# STM32G474RBT6.net
KiCad netlist of a schematic drawn in EasyEDA Pro
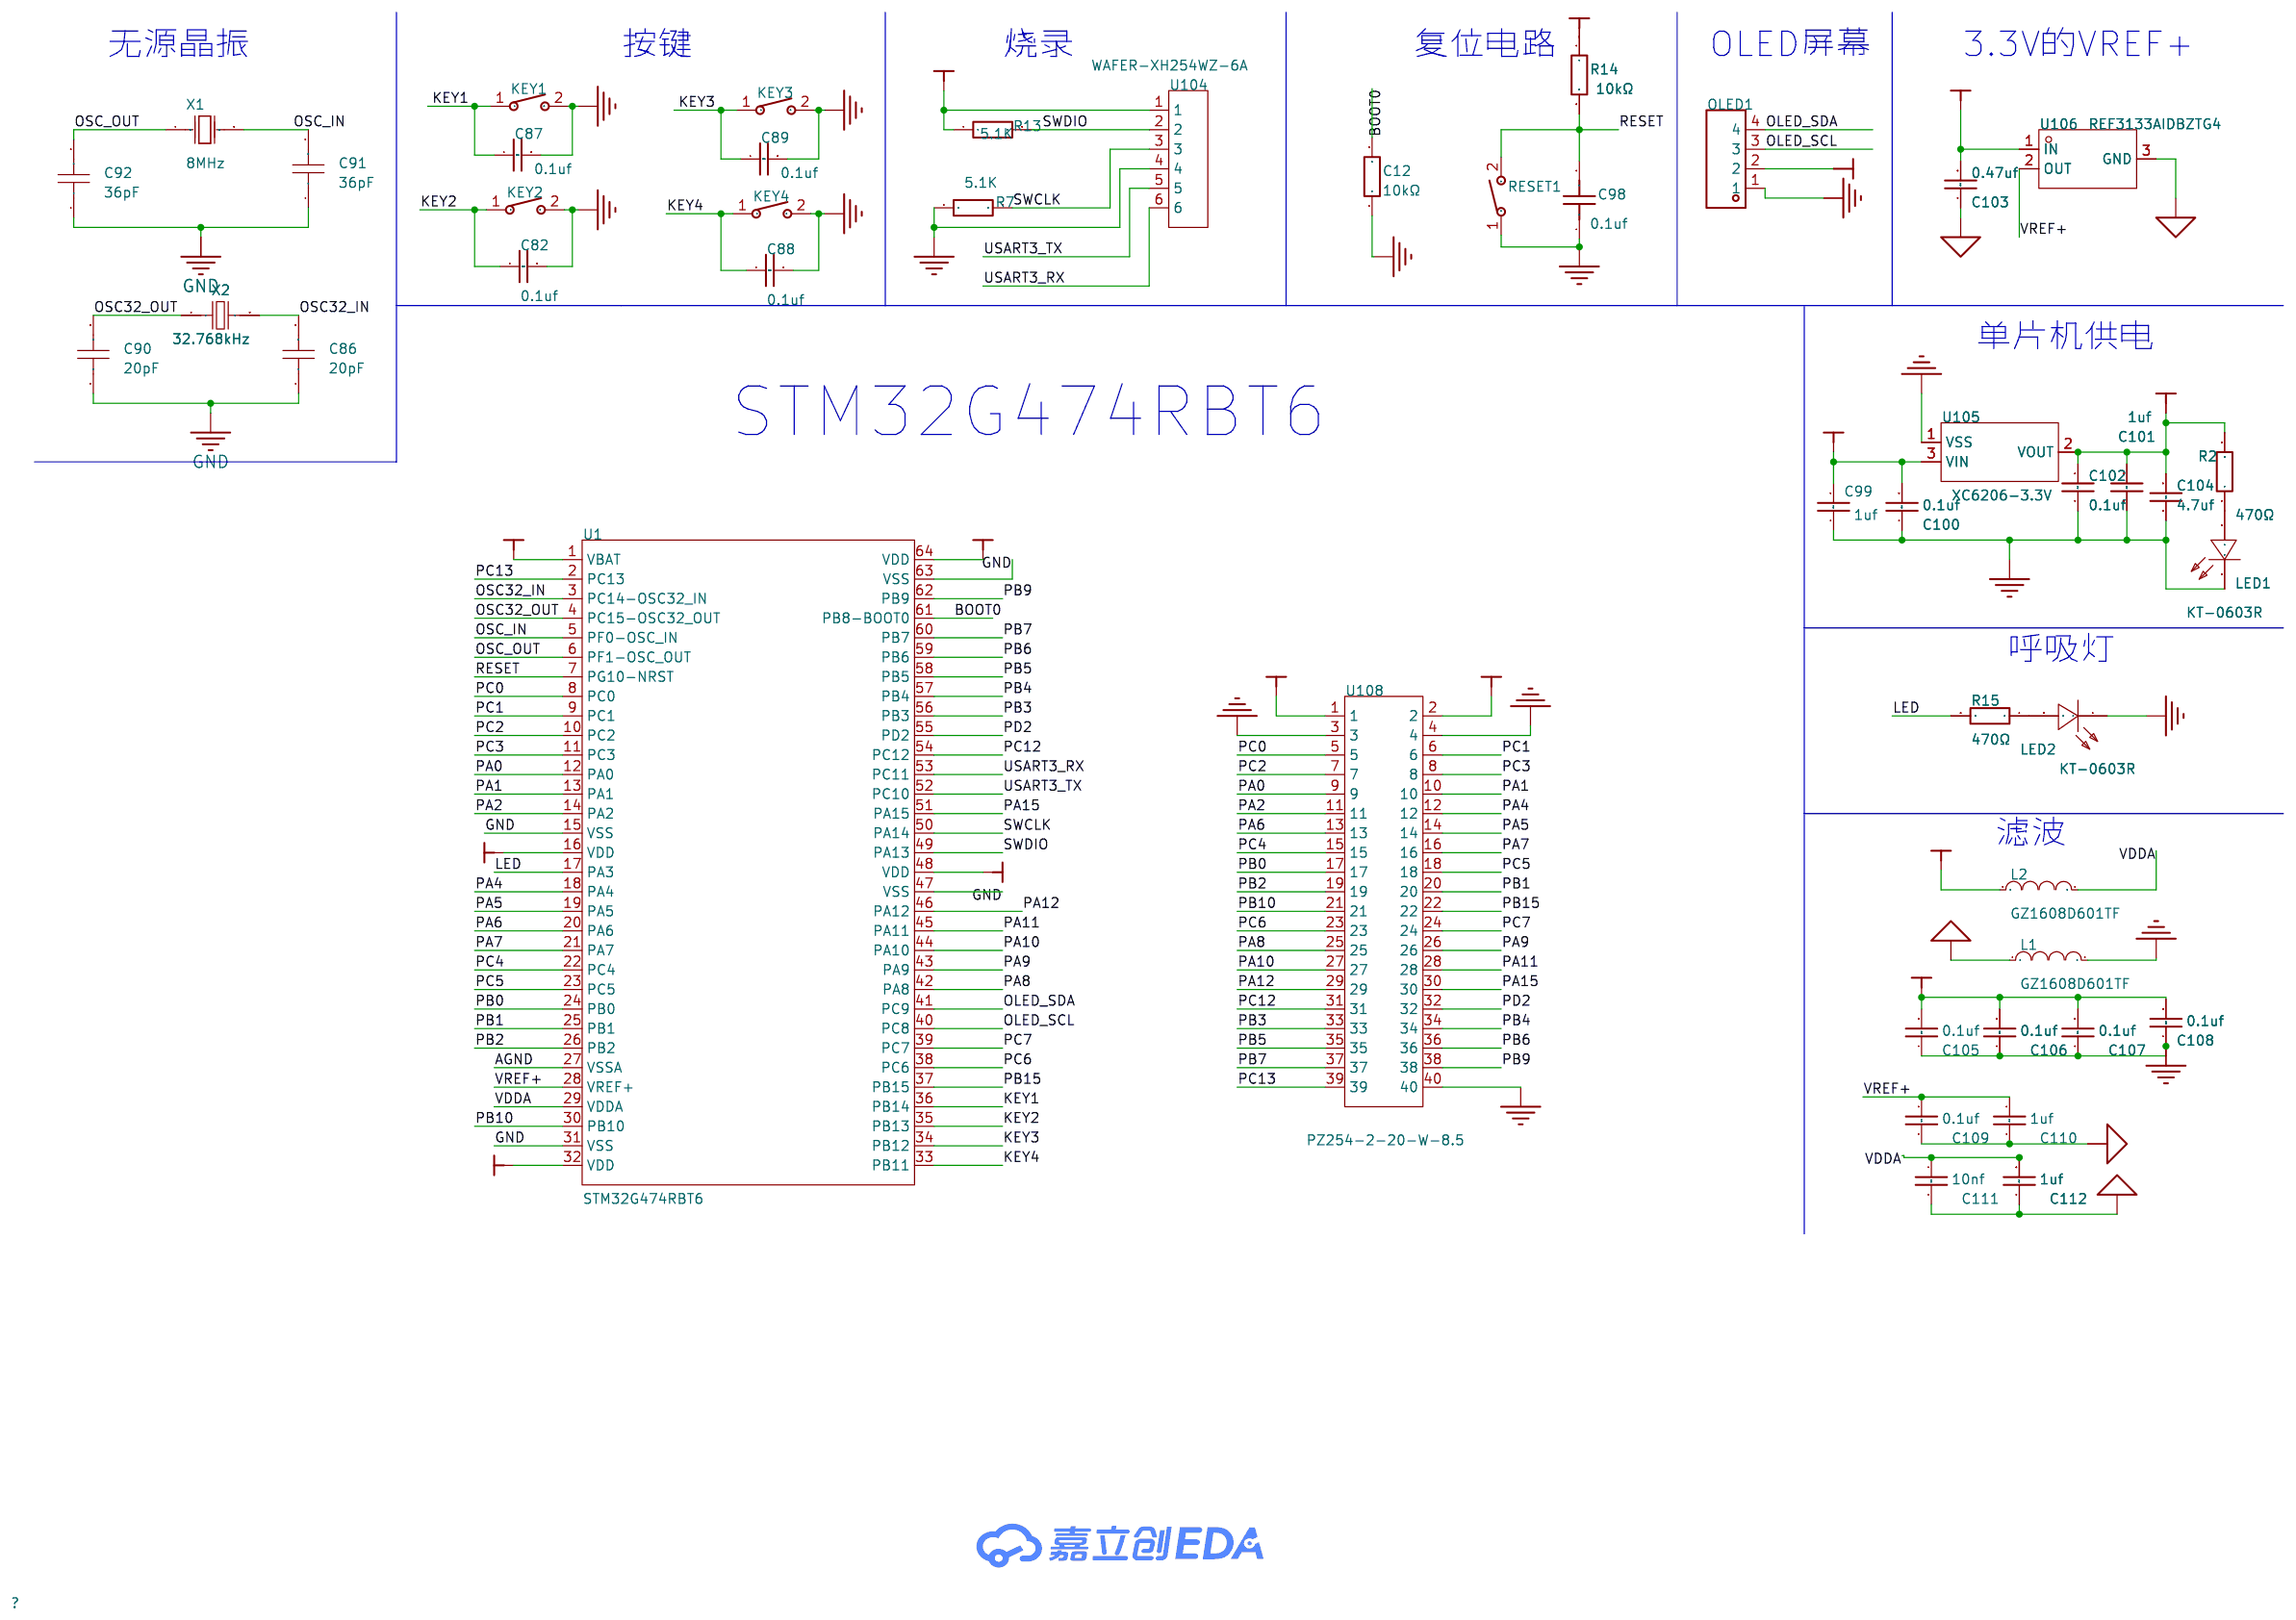
[diagram p0: schematic sheet]

(export (version "E")
  (design (tool "Eeschema 10.0.6"))
  (components
    (comp (ref "C12")
      (value "10kΩ")
      (footprint "easyedapro:R0805")
      (fields
        (field (name "Manufacturer Part") "0805W8F1002T5E")
        (field (name "Manufacturer") "UNI-ROYAL(厚声)")
      )
      (libsource (lib "easyedapro") (part "0805W8F1002T5E"))
    )
    (comp (ref "C82")
      (value "0.1uf")
      (footprint "easyedapro:C0603")
      (libsource (lib "easyedapro") (part "C0603"))
    )
    (comp (ref "C86")
      (value "20pF")
      (footprint "easyedapro:C0603")
      (description "容值:47pF;精度:±5%;额定电压:100V;温度系数:C0G;")
      (fields
        (field (name "Manufacturer Part") "CAI0603C0G470J101JT")
        (field (name "Manufacturer") "HRE(芯声)")
      )
      (libsource (lib "easyedapro") (part "CAI0603C0G470J101JT"))
    )
    (comp (ref "C87")
      (value "0.1uf")
      (footprint "easyedapro:C0603")
      (libsource (lib "easyedapro") (part "C0603"))
    )
    (comp (ref "C88")
      (value "0.1uf")
      (footprint "easyedapro:C0603")
      (libsource (lib "easyedapro") (part "C0603"))
    )
    (comp (ref "C89")
      (value "0.1uf")
      (footprint "easyedapro:C0603")
      (libsource (lib "easyedapro") (part "C0603"))
    )
    (comp (ref "C90")
      (value "20pF")
      (footprint "easyedapro:C0603")
      (description "容值:47pF;精度:±5%;额定电压:100V;温度系数:C0G;")
      (fields
        (field (name "Manufacturer Part") "CAI0603C0G470J101JT")
        (field (name "Manufacturer") "HRE(芯声)")
      )
      (libsource (lib "easyedapro") (part "CAI0603C0G470J101JT"))
    )
    (comp (ref "C91")
      (value "36pF")
      (footprint "easyedapro:C0603")
      (description "容值:47pF;精度:±5%;额定电压:100V;温度系数:C0G;")
      (fields
        (field (name "Manufacturer Part") "CAI0603C0G470J101JT")
        (field (name "Manufacturer") "HRE(芯声)")
      )
      (libsource (lib "easyedapro") (part "CAI0603C0G470J101JT"))
    )
    (comp (ref "C92")
      (value "36pF")
      (footprint "easyedapro:C0603")
      (description "容值:47pF;精度:±5%;额定电压:100V;温度系数:C0G;")
      (fields
        (field (name "Manufacturer Part") "CAI0603C0G470J101JT")
        (field (name "Manufacturer") "HRE(芯声)")
      )
      (libsource (lib "easyedapro") (part "CAI0603C0G470J101JT"))
    )
    (comp (ref "C98") (value "0.1uf") (footprint "easyedapro:电容") (libsource (lib "easyedapro") (part "电容")))
    (comp (ref "C99")
      (value "1uf")
      (footprint "easyedapro:C0603")
      (libsource (lib "easyedapro") (part "C0603"))
    )
    (comp (ref "C100")
      (value "0.1uf")
      (footprint "easyedapro:C0603")
      (libsource (lib "easyedapro") (part "C0603"))
    )
    (comp (ref "C101")
      (value "1uf")
      (footprint "easyedapro:C0603")
      (libsource (lib "easyedapro") (part "C0603"))
    )
    (comp (ref "C102")
      (value "0.1uf")
      (footprint "easyedapro:C0603")
      (libsource (lib "easyedapro") (part "C0603"))
    )
    (comp (ref "C103")
      (value "0.47uf")
      (footprint "easyedapro:C0603")
      (libsource (lib "easyedapro") (part "C0603"))
    )
    (comp (ref "C104")
      (value "4.7uf")
      (footprint "easyedapro:C0603")
      (libsource (lib "easyedapro") (part "C0603"))
    )
    (comp (ref "C105")
      (value "0.1uf")
      (footprint "easyedapro:C0603")
      (libsource (lib "easyedapro") (part "C0603"))
    )
    (comp (ref "C106")
      (value "0.1uf")
      (footprint "easyedapro:C0603")
      (libsource (lib "easyedapro") (part "C0603"))
    )
    (comp (ref "C107")
      (value "0.1uf")
      (footprint "easyedapro:C0603")
      (libsource (lib "easyedapro") (part "C0603"))
    )
    (comp (ref "C108")
      (value "0.1uf")
      (footprint "easyedapro:C0603")
      (libsource (lib "easyedapro") (part "C0603"))
    )
    (comp (ref "C109")
      (value "0.1uf")
      (footprint "easyedapro:C0603")
      (libsource (lib "easyedapro") (part "C0603"))
    )
    (comp (ref "C110")
      (value "1uf")
      (footprint "easyedapro:C0603")
      (libsource (lib "easyedapro") (part "C0603"))
    )
    (comp (ref "C111")
      (value "10nf")
      (footprint "easyedapro:C0603")
      (libsource (lib "easyedapro") (part "C0603"))
    )
    (comp (ref "C112")
      (value "1uf")
      (footprint "easyedapro:C0603")
      (libsource (lib "easyedapro") (part "C0603"))
    )
    (comp (ref "KEY1")
      (value "TS6643WS 250gf 072")
      (footprint "easyedapro:SW-SMD_L6.0-W6.0-P6.00-LS6.8")
      (fields (field (name "Manufacturer") "SHOU HAN(首韩)"))
      (libsource (lib "easyedapro") (part "TS6643WS 250GF 072"))
    )
    (comp (ref "KEY2")
      (value "TS6643WS 250gf 072")
      (footprint "easyedapro:SW-SMD_L6.0-W6.0-P6.00-LS6.8")
      (fields (field (name "Manufacturer") "SHOU HAN(首韩)"))
      (libsource (lib "easyedapro") (part "TS6643WS 250GF 072"))
    )
    (comp (ref "KEY3")
      (value "TS6643WS 250gf 072")
      (footprint "easyedapro:SW-SMD_L6.0-W6.0-P6.00-LS6.8")
      (fields (field (name "Manufacturer") "SHOU HAN(首韩)"))
      (libsource (lib "easyedapro") (part "TS6643WS 250GF 072"))
    )
    (comp (ref "KEY4")
      (value "TS6643WS 250gf 072")
      (footprint "easyedapro:SW-SMD_L6.0-W6.0-P6.00-LS6.8")
      (fields (field (name "Manufacturer") "SHOU HAN(首韩)"))
      (libsource (lib "easyedapro") (part "TS6643WS 250GF 072"))
    )
    (comp (ref "L1")
      (value "GZ1608D601TF")
      (footprint "easyedapro:L0603")
      (description "阻抗@频率:600Ω@100MHz;误差:±25%;直流电阻(DCR):450mΩ;")
      (fields (field (name "Manufacturer") "Sunlord(顺络)"))
      (libsource (lib "easyedapro") (part "GZ1608D601TF"))
    )
    (comp (ref "L2")
      (value "GZ1608D601TF")
      (footprint "easyedapro:L0603")
      (description "阻抗@频率:600Ω@100MHz;误差:±25%;直流电阻(DCR):450mΩ;")
      (fields (field (name "Manufacturer") "Sunlord(顺络)"))
      (libsource (lib "easyedapro") (part "GZ1608D601TF"))
    )
    (comp (ref "LED1")
      (value "KT-0603R")
      (footprint "easyedapro:LED0603-RD")
      (fields (field (name "Manufacturer") "KENTO"))
      (libsource (lib "easyedapro") (part "KT-0603R"))
    )
    (comp (ref "LED2")
      (value "KT-0603R")
      (footprint "easyedapro:LED0603-RD")
      (fields (field (name "Manufacturer") "KENTO"))
      (libsource (lib "easyedapro") (part "KT-0603R"))
    )
    (comp (ref "OLED1")
      (value "2.54-1*4P母")
      (footprint "easyedapro:HDR-TH_4P-P2.54-V-F")
      (fields (field (name "Manufacturer") "BOOMELE(博穆精密)"))
      (libsource (lib "easyedapro") (part "2.54-1*4P母"))
    )
    (comp (ref "R2")
      (value "470Ω")
      (footprint "easyedapro:R0805")
      (description "电阻类型:厚膜电阻;阻值:5.1kΩ;精度:±1%;功率:125mW;最大工作电压:150V;温度系数:±100ppm/℃;")
      (fields
        (field (name "Manufacturer Part") "0805W8F5101T5E")
        (field (name "Manufacturer") "UNI-ROYAL(厚声)")
      )
      (libsource (lib "easyedapro") (part "0805W8F5101T5E"))
    )
    (comp (ref "R7") (value "5.1K") (footprint "easyedapro:电阻") (libsource (lib "easyedapro") (part "电阻")))
    (comp (ref "R13") (value "5.1K") (footprint "easyedapro:电阻") (libsource (lib "easyedapro") (part "电阻")))
    (comp (ref "R14") (value "10kΩ") (footprint "easyedapro:电阻") (libsource (lib "easyedapro") (part "电阻")))
    (comp (ref "R15")
      (value "470Ω")
      (footprint "easyedapro:R0805")
      (description "电阻类型:厚膜电阻;阻值:5.1kΩ;精度:±1%;功率:125mW;最大工作电压:150V;温度系数:±100ppm/℃;")
      (fields
        (field (name "Manufacturer Part") "0805W8F5101T5E")
        (field (name "Manufacturer") "UNI-ROYAL(厚声)")
      )
      (libsource (lib "easyedapro") (part "0805W8F5101T5E"))
    )
    (comp (ref "RESET1")
      (value "TS6643WS 250gf 072")
      (footprint "easyedapro:SW-SMD_L6.0-W6.0-P6.00-LS6.8")
      (fields (field (name "Manufacturer") "SHOU HAN(首韩)"))
      (libsource (lib "easyedapro") (part "TS6643WS 250GF 072"))
    )
    (comp (ref "U1")
      (value "STM32G474RBT6")
      (footprint "easyedapro:LQFP-64_L10.0-W10.0-P0.50-LS12.0-BL")
      (description "CPU内核:ARM-M4;CPU最大主频:170MHz;应用领域:-;")
      (fields (field (name "Manufacturer") "ST(意法半导体)"))
      (libsource (lib "easyedapro") (part "STM32G474RBT6"))
    )
    (comp (ref "U104")
      (value "WAFER-XH254WZ-6A")
      (footprint "easyedapro:CONN-TH_6P-P2.50_WAFER-XH254WZ-6A")
      (description "插针结构:1x6P;间距:2.54mm;安装方式:弯插;参考系列:XH;总PIN数:6P;排数:1;每排PIN数:6;额定电流:3A;触头材质:黄铜;工作温度:-25°C~+85°C;")
      (fields (field (name "Manufacturer") "HANBO(汉博)"))
      (libsource (lib "easyedapro") (part "WAFER-XH254WZ-6A"))
    )
    (comp (ref "U105")
      (value "XC6206-3.3V")
      (footprint "easyedapro:SSOT-3_L2.9-W1.6-P0.95-LS2.8-BR")
      (description "输出类型:固定;工作电压:6V;输出电压:3.3V;输出电流:250mA;电源纹波抑制比(PSRR):-;输出极性:正极;")
      (fields (field (name "Manufacturer") "YONGYUTAI(永裕泰)"))
      (libsource (lib "easyedapro") (part "XC6206-3.3V"))
    )
    (comp (ref "U106")
      (value "REF3133AIDBZTG4")
      (footprint "easyedapro:SOT-23-3_L2.9-W1.4-0.95-LS2.5-BR")
      (description "输出类型:固定;工作电压:3.35V~5.5V;输出电压:3.3V;输出电流:10mA;精度:±0.2%;")
      (fields (field (name "Manufacturer") "TI(德州仪器)"))
      (libsource (lib "easyedapro") (part "REF3133AIDBZTG4"))
    )
    (comp (ref "U108")
      (value "PZ254-2-20-W-8.5")
      (footprint "easyedapro:HDR-TH_40P-P2.54-H-M-R2-C20-S2.54-W12.9-N")
      (fields (field (name "Manufacturer") "HCTL(华灿天禄)"))
      (libsource (lib "easyedapro") (part "PZ254-2-20-W-8.5KK"))
    )
    (comp (ref "X1")
      (value "8MHz")
      (footprint "easyedapro:CRYSTAL-SMD_L5.0-W3.2")
      (description "晶振类型:贴片晶振;频率:8MHz;常温频差:±10ppm;负载电容:20pF;频率稳定度:±20ppm;")
      (fields (field (name "Manufacturer Part") "X50328MSB2GI") (field (name "Manufacturer") "YXC(扬兴晶振)"))
      (libsource (lib "easyedapro") (part "X50328MSB2GI"))
    )
    (comp (ref "X2")
      (value "32.768kHz")
      (footprint "easyedapro:FC-135R_L3.2-W1.5")
      (description "晶振类型:贴片无源晶振;频率:32.768kHz;频率公差:±20ppm;频率稳定度:-;负载电容:12.5pF;等效串联电阻(ESR):70kΩ;工作温度:-40~+85;")
      (fields (field (name "Manufacturer Part") "Q13FC1350000400") (field (name "Manufacturer") "EPSON(爱普生)"))
      (libsource (lib "easyedapro") (part "Q13FC1350000400"))
    )
  )
  (nets
    (net (code "1") (name "/BOOT0") (class "Default")
      (node (ref "C12") (pin "2") (pinfunction "2_2") (pintype "input"))
      (node (ref "U1") (pin "61") (pinfunction "PB8-BOOT0_61") (pintype "unspecified"))
    )
    (net (code "2") (name "/KEY1") (class "Default")
      (node (ref "C87") (pin "1") (pinfunction "1_1") (pintype "input"))
      (node (ref "KEY1") (pin "1") (pinfunction "1_1") (pintype "unspecified"))
      (node (ref "U1") (pin "36") (pinfunction "PB14_36") (pintype "unspecified"))
    )
    (net (code "3") (name "/KEY2") (class "Default")
      (node (ref "C82") (pin "1") (pinfunction "1_1") (pintype "input"))
      (node (ref "KEY2") (pin "1") (pinfunction "1_1") (pintype "unspecified"))
      (node (ref "U1") (pin "35") (pinfunction "PB13_35") (pintype "unspecified"))
    )
    (net (code "4") (name "/KEY3") (class "Default")
      (node (ref "C89") (pin "1") (pinfunction "1_1") (pintype "input"))
      (node (ref "KEY3") (pin "1") (pinfunction "1_1") (pintype "unspecified"))
      (node (ref "U1") (pin "34") (pinfunction "PB12_34") (pintype "unspecified"))
    )
    (net (code "5") (name "/KEY4") (class "Default")
      (node (ref "C88") (pin "1") (pinfunction "1_1") (pintype "input"))
      (node (ref "KEY4") (pin "1") (pinfunction "1_1") (pintype "unspecified"))
      (node (ref "U1") (pin "33") (pinfunction "PB11_33") (pintype "unspecified"))
    )
    (net (code "6") (name "/LED") (class "Default")
      (node (ref "R15") (pin "2") (pinfunction "2_2") (pintype "input"))
      (node (ref "U1") (pin "17") (pinfunction "PA3_17") (pintype "unspecified"))
    )
    (net (code "7") (name "/OLED_SCL") (class "Default")
      (node (ref "OLED1") (pin "3") (pinfunction "3_3") (pintype "unspecified"))
      (node (ref "U1") (pin "40") (pinfunction "PC8_40") (pintype "unspecified"))
    )
    (net (code "8") (name "/OLED_SDA") (class "Default")
      (node (ref "OLED1") (pin "4") (pinfunction "4_4") (pintype "unspecified"))
      (node (ref "U1") (pin "41") (pinfunction "PC9_41") (pintype "unspecified"))
    )
    (net (code "9") (name "/OSC32_IN") (class "Default")
      (node (ref "C86") (pin "2") (pinfunction "2_2") (pintype "unspecified"))
      (node (ref "U1") (pin "3") (pinfunction "PC14-OSC32_IN_3") (pintype "unspecified"))
      (node (ref "X2") (pin "2") (pinfunction "2_2") (pintype "input"))
    )
    (net (code "10") (name "/OSC32_OUT") (class "Default")
      (node (ref "C90") (pin "2") (pinfunction "2_2") (pintype "unspecified"))
      (node (ref "U1") (pin "4") (pinfunction "PC15-OSC32_OUT_4") (pintype "unspecified"))
      (node (ref "X2") (pin "1") (pinfunction "1_1") (pintype "input"))
    )
    (net (code "11") (name "/OSC_IN") (class "Default")
      (node (ref "C91") (pin "2") (pinfunction "2_2") (pintype "unspecified"))
      (node (ref "U1") (pin "5") (pinfunction "PF0-OSC_IN_5") (pintype "unspecified"))
      (node (ref "X1") (pin "2") (pinfunction "OSC2_2") (pintype "input"))
    )
    (net (code "12") (name "/OSC_OUT") (class "Default")
      (node (ref "C92") (pin "2") (pinfunction "2_2") (pintype "unspecified"))
      (node (ref "U1") (pin "6") (pinfunction "PF1-OSC_OUT_6") (pintype "unspecified"))
      (node (ref "X1") (pin "1") (pinfunction "OSC1_1") (pintype "input"))
    )
    (net (code "13") (name "/PA0") (class "Default")
      (node (ref "U1") (pin "12") (pinfunction "PA0_12") (pintype "unspecified"))
      (node (ref "U108") (pin "9") (pinfunction "9_9") (pintype "unspecified"))
    )
    (net (code "14") (name "/PA1") (class "Default")
      (node (ref "U1") (pin "13") (pinfunction "PA1_13") (pintype "unspecified"))
      (node (ref "U108") (pin "10") (pinfunction "10_10") (pintype "unspecified"))
    )
    (net (code "15") (name "/PA2") (class "Default")
      (node (ref "U1") (pin "14") (pinfunction "PA2_14") (pintype "unspecified"))
      (node (ref "U108") (pin "11") (pinfunction "11_11") (pintype "unspecified"))
    )
    (net (code "16") (name "/PA4") (class "Default")
      (node (ref "U1") (pin "18") (pinfunction "PA4_18") (pintype "unspecified"))
      (node (ref "U108") (pin "12") (pinfunction "12_12") (pintype "unspecified"))
    )
    (net (code "17") (name "/PA5") (class "Default")
      (node (ref "U1") (pin "19") (pinfunction "PA5_19") (pintype "unspecified"))
      (node (ref "U108") (pin "14") (pinfunction "14_14") (pintype "unspecified"))
    )
    (net (code "18") (name "/PA6") (class "Default")
      (node (ref "U1") (pin "20") (pinfunction "PA6_20") (pintype "unspecified"))
      (node (ref "U108") (pin "13") (pinfunction "13_13") (pintype "unspecified"))
    )
    (net (code "19") (name "/PA7") (class "Default")
      (node (ref "U1") (pin "21") (pinfunction "PA7_21") (pintype "unspecified"))
      (node (ref "U108") (pin "16") (pinfunction "16_16") (pintype "unspecified"))
    )
    (net (code "20") (name "/PA8") (class "Default")
      (node (ref "U1") (pin "42") (pinfunction "PA8_42") (pintype "unspecified"))
      (node (ref "U108") (pin "25") (pinfunction "25_25") (pintype "unspecified"))
    )
    (net (code "21") (name "/PA9") (class "Default")
      (node (ref "U1") (pin "43") (pinfunction "PA9_43") (pintype "unspecified"))
      (node (ref "U108") (pin "26") (pinfunction "26_26") (pintype "unspecified"))
    )
    (net (code "22") (name "/PA10") (class "Default")
      (node (ref "U1") (pin "44") (pinfunction "PA10_44") (pintype "unspecified"))
      (node (ref "U108") (pin "27") (pinfunction "27_27") (pintype "unspecified"))
    )
    (net (code "23") (name "/PA11") (class "Default")
      (node (ref "U1") (pin "45") (pinfunction "PA11_45") (pintype "unspecified"))
      (node (ref "U108") (pin "28") (pinfunction "28_28") (pintype "unspecified"))
    )
    (net (code "24") (name "/PA12") (class "Default")
      (node (ref "U1") (pin "46") (pinfunction "PA12_46") (pintype "unspecified"))
      (node (ref "U108") (pin "29") (pinfunction "29_29") (pintype "unspecified"))
    )
    (net (code "25") (name "/PA15") (class "Default")
      (node (ref "U1") (pin "51") (pinfunction "PA15_51") (pintype "unspecified"))
      (node (ref "U108") (pin "30") (pinfunction "30_30") (pintype "unspecified"))
    )
    (net (code "26") (name "/PB0") (class "Default")
      (node (ref "U1") (pin "24") (pinfunction "PB0_24") (pintype "unspecified"))
      (node (ref "U108") (pin "17") (pinfunction "17_17") (pintype "unspecified"))
    )
    (net (code "27") (name "/PB1") (class "Default")
      (node (ref "U1") (pin "25") (pinfunction "PB1_25") (pintype "unspecified"))
      (node (ref "U108") (pin "20") (pinfunction "20_20") (pintype "unspecified"))
    )
    (net (code "28") (name "/PB2") (class "Default")
      (node (ref "U1") (pin "26") (pinfunction "PB2_26") (pintype "unspecified"))
      (node (ref "U108") (pin "19") (pinfunction "19_19") (pintype "unspecified"))
    )
    (net (code "29") (name "/PB3") (class "Default")
      (node (ref "U1") (pin "56") (pinfunction "PB3_56") (pintype "unspecified"))
      (node (ref "U108") (pin "33") (pinfunction "33_33") (pintype "unspecified"))
    )
    (net (code "30") (name "/PB4") (class "Default")
      (node (ref "U1") (pin "57") (pinfunction "PB4_57") (pintype "unspecified"))
      (node (ref "U108") (pin "34") (pinfunction "34_34") (pintype "unspecified"))
    )
    (net (code "31") (name "/PB5") (class "Default")
      (node (ref "U1") (pin "58") (pinfunction "PB5_58") (pintype "unspecified"))
      (node (ref "U108") (pin "35") (pinfunction "35_35") (pintype "unspecified"))
    )
    (net (code "32") (name "/PB6") (class "Default")
      (node (ref "U1") (pin "59") (pinfunction "PB6_59") (pintype "unspecified"))
      (node (ref "U108") (pin "36") (pinfunction "36_36") (pintype "unspecified"))
    )
    (net (code "33") (name "/PB7") (class "Default")
      (node (ref "U1") (pin "60") (pinfunction "PB7_60") (pintype "unspecified"))
      (node (ref "U108") (pin "37") (pinfunction "37_37") (pintype "unspecified"))
    )
    (net (code "34") (name "/PB9") (class "Default")
      (node (ref "U1") (pin "62") (pinfunction "PB9_62") (pintype "unspecified"))
      (node (ref "U108") (pin "38") (pinfunction "38_38") (pintype "unspecified"))
    )
    (net (code "35") (name "/PB10") (class "Default")
      (node (ref "U1") (pin "30") (pinfunction "PB10_30") (pintype "unspecified"))
      (node (ref "U108") (pin "21") (pinfunction "21_21") (pintype "unspecified"))
    )
    (net (code "36") (name "/PB15") (class "Default")
      (node (ref "U1") (pin "37") (pinfunction "PB15_37") (pintype "unspecified"))
      (node (ref "U108") (pin "22") (pinfunction "22_22") (pintype "unspecified"))
    )
    (net (code "37") (name "/PC0") (class "Default")
      (node (ref "U1") (pin "8") (pinfunction "PC0_8") (pintype "unspecified"))
      (node (ref "U108") (pin "5") (pinfunction "5_5") (pintype "unspecified"))
    )
    (net (code "38") (name "/PC1") (class "Default")
      (node (ref "U1") (pin "9") (pinfunction "PC1_9") (pintype "unspecified"))
      (node (ref "U108") (pin "6") (pinfunction "6_6") (pintype "unspecified"))
    )
    (net (code "39") (name "/PC2") (class "Default")
      (node (ref "U1") (pin "10") (pinfunction "PC2_10") (pintype "unspecified"))
      (node (ref "U108") (pin "7") (pinfunction "7_7") (pintype "unspecified"))
    )
    (net (code "40") (name "/PC3") (class "Default")
      (node (ref "U1") (pin "11") (pinfunction "PC3_11") (pintype "unspecified"))
      (node (ref "U108") (pin "8") (pinfunction "8_8") (pintype "unspecified"))
    )
    (net (code "41") (name "/PC4") (class "Default")
      (node (ref "U1") (pin "22") (pinfunction "PC4_22") (pintype "unspecified"))
      (node (ref "U108") (pin "15") (pinfunction "15_15") (pintype "unspecified"))
    )
    (net (code "42") (name "/PC5") (class "Default")
      (node (ref "U1") (pin "23") (pinfunction "PC5_23") (pintype "unspecified"))
      (node (ref "U108") (pin "18") (pinfunction "18_18") (pintype "unspecified"))
    )
    (net (code "43") (name "/PC6") (class "Default")
      (node (ref "U1") (pin "38") (pinfunction "PC6_38") (pintype "unspecified"))
      (node (ref "U108") (pin "23") (pinfunction "23_23") (pintype "unspecified"))
    )
    (net (code "44") (name "/PC7") (class "Default")
      (node (ref "U1") (pin "39") (pinfunction "PC7_39") (pintype "unspecified"))
      (node (ref "U108") (pin "24") (pinfunction "24_24") (pintype "unspecified"))
    )
    (net (code "45") (name "/PC12") (class "Default")
      (node (ref "U1") (pin "54") (pinfunction "PC12_54") (pintype "unspecified"))
      (node (ref "U108") (pin "31") (pinfunction "31_31") (pintype "unspecified"))
    )
    (net (code "46") (name "/PC13") (class "Default")
      (node (ref "U1") (pin "2") (pinfunction "PC13_2") (pintype "unspecified"))
      (node (ref "U108") (pin "39") (pinfunction "39_39") (pintype "unspecified"))
    )
    (net (code "47") (name "/PD2") (class "Default")
      (node (ref "U1") (pin "55") (pinfunction "PD2_55") (pintype "unspecified"))
      (node (ref "U108") (pin "32") (pinfunction "32_32") (pintype "unspecified"))
    )
    (net (code "48") (name "/RESET") (class "Default")
      (node (ref "C98") (pin "2") (pinfunction "2_2") (pintype "input"))
      (node (ref "R14") (pin "2") (pinfunction "2_2") (pintype "input"))
      (node (ref "RESET1") (pin "2") (pinfunction "2_2") (pintype "unspecified"))
      (node (ref "U1") (pin "7") (pinfunction "PG10-NRST_7") (pintype "unspecified"))
    )
    (net (code "49") (name "/SWCLK") (class "Default")
      (node (ref "R7") (pin "2") (pinfunction "2_2") (pintype "input"))
      (node (ref "U1") (pin "50") (pinfunction "PA14_50") (pintype "unspecified"))
      (node (ref "U104") (pin "3") (pinfunction "3_3") (pintype "unspecified"))
    )
    (net (code "50") (name "/SWDIO") (class "Default")
      (node (ref "R13") (pin "2") (pinfunction "2_2") (pintype "input"))
      (node (ref "U1") (pin "49") (pinfunction "PA13_49") (pintype "unspecified"))
      (node (ref "U104") (pin "2") (pinfunction "2_2") (pintype "unspecified"))
    )
    (net (code "51") (name "/USART3_RX") (class "Default")
      (node (ref "U1") (pin "53") (pinfunction "PC11_53") (pintype "unspecified"))
      (node (ref "U104") (pin "6") (pinfunction "6_6") (pintype "unspecified"))
    )
    (net (code "52") (name "/USART3_TX") (class "Default")
      (node (ref "U1") (pin "52") (pinfunction "PC10_52") (pintype "unspecified"))
      (node (ref "U104") (pin "5") (pinfunction "5_5") (pintype "unspecified"))
    )
    (net (code "53") (name "/VDDA") (class "Default")
      (node (ref "C111") (pin "2") (pinfunction "2_2") (pintype "input"))
      (node (ref "C112") (pin "2") (pinfunction "2_2") (pintype "input"))
      (node (ref "L2") (pin "2") (pinfunction "2_2") (pintype "unspecified"))
      (node (ref "U1") (pin "29") (pinfunction "VDDA_29") (pintype "unspecified"))
    )
    (net (code "54") (name "/VREF+") (class "Default")
      (node (ref "C109") (pin "2") (pinfunction "2_2") (pintype "input"))
      (node (ref "C110") (pin "2") (pinfunction "2_2") (pintype "input"))
      (node (ref "U1") (pin "28") (pinfunction "VREF+_28") (pintype "unspecified"))
      (node (ref "U106") (pin "2") (pinfunction "OUT_2") (pintype "unspecified"))
    )
    (net (code "55") (name "3V3") (class "Default")
      (node (ref "C101") (pin "2") (pinfunction "2_2") (pintype "input"))
      (node (ref "C102") (pin "2") (pinfunction "2_2") (pintype "input"))
      (node (ref "C104") (pin "2") (pinfunction "2_2") (pintype "input"))
      (node (ref "C105") (pin "2") (pinfunction "2_2") (pintype "input"))
      (node (ref "C106") (pin "2") (pinfunction "2_2") (pintype "input"))
      (node (ref "C107") (pin "2") (pinfunction "2_2") (pintype "input"))
      (node (ref "C108") (pin "2") (pinfunction "2_2") (pintype "input"))
      (node (ref "L2") (pin "1") (pinfunction "1_1") (pintype "unspecified"))
      (node (ref "OLED1") (pin "2") (pinfunction "2_2") (pintype "unspecified"))
      (node (ref "R13") (pin "1") (pinfunction "1_1") (pintype "input"))
      (node (ref "R14") (pin "1") (pinfunction "1_1") (pintype "input"))
      (node (ref "R2") (pin "2") (pinfunction "2_2") (pintype "input"))
      (node (ref "U1") (pin "1") (pinfunction "VBAT_1") (pintype "unspecified"))
      (node (ref "U1") (pin "16") (pinfunction "VDD_16") (pintype "unspecified"))
      (node (ref "U1") (pin "32") (pinfunction "VDD_32") (pintype "unspecified"))
      (node (ref "U1") (pin "48") (pinfunction "VDD_48") (pintype "unspecified"))
      (node (ref "U1") (pin "64") (pinfunction "VDD_64") (pintype "unspecified"))
      (node (ref "U104") (pin "1") (pinfunction "1_1") (pintype "unspecified"))
      (node (ref "U105") (pin "2") (pinfunction "VOUT_2") (pintype "unspecified"))
    )
    (net (code "56") (name "5V") (class "Default")
      (node (ref "C100") (pin "2") (pinfunction "2_2") (pintype "input"))
      (node (ref "C103") (pin "2") (pinfunction "2_2") (pintype "input"))
      (node (ref "C99") (pin "2") (pinfunction "2_2") (pintype "input"))
      (node (ref "U105") (pin "3") (pinfunction "VIN_3") (pintype "unspecified"))
      (node (ref "U106") (pin "1") (pinfunction "IN_1") (pintype "unspecified"))
      (node (ref "U108") (pin "1") (pinfunction "1_1") (pintype "unspecified"))
      (node (ref "U108") (pin "2") (pinfunction "2_2") (pintype "unspecified"))
    )
    (net (code "57") (name "AGND") (class "Default")
      (node (ref "C103") (pin "1") (pinfunction "1_1") (pintype "input"))
      (node (ref "C109") (pin "1") (pinfunction "1_1") (pintype "input"))
      (node (ref "C110") (pin "1") (pinfunction "1_1") (pintype "input"))
      (node (ref "C111") (pin "1") (pinfunction "1_1") (pintype "input"))
      (node (ref "C112") (pin "1") (pinfunction "1_1") (pintype "input"))
      (node (ref "L1") (pin "1") (pinfunction "1_1") (pintype "unspecified"))
      (node (ref "U1") (pin "27") (pinfunction "VSSA_27") (pintype "unspecified"))
      (node (ref "U106") (pin "3") (pinfunction "GND_3") (pintype "unspecified"))
    )
    (net (code "58") (name "GND") (class "Default")
      (node (ref "C100") (pin "1") (pinfunction "1_1") (pintype "input"))
      (node (ref "C101") (pin "1") (pinfunction "1_1") (pintype "input"))
      (node (ref "C102") (pin "1") (pinfunction "1_1") (pintype "input"))
      (node (ref "C104") (pin "1") (pinfunction "1_1") (pintype "input"))
      (node (ref "C105") (pin "1") (pinfunction "1_1") (pintype "input"))
      (node (ref "C106") (pin "1") (pinfunction "1_1") (pintype "input"))
      (node (ref "C107") (pin "1") (pinfunction "1_1") (pintype "input"))
      (node (ref "C108") (pin "1") (pinfunction "1_1") (pintype "input"))
      (node (ref "C12") (pin "1") (pinfunction "1_1") (pintype "input"))
      (node (ref "C82") (pin "2") (pinfunction "2_2") (pintype "input"))
      (node (ref "C86") (pin "1") (pinfunction "1_1") (pintype "unspecified"))
      (node (ref "C87") (pin "2") (pinfunction "2_2") (pintype "input"))
      (node (ref "C88") (pin "2") (pinfunction "2_2") (pintype "input"))
      (node (ref "C89") (pin "2") (pinfunction "2_2") (pintype "input"))
      (node (ref "C90") (pin "1") (pinfunction "1_1") (pintype "unspecified"))
      (node (ref "C91") (pin "1") (pinfunction "1_1") (pintype "unspecified"))
      (node (ref "C92") (pin "1") (pinfunction "1_1") (pintype "unspecified"))
      (node (ref "C98") (pin "1") (pinfunction "1_1") (pintype "input"))
      (node (ref "C99") (pin "1") (pinfunction "1_1") (pintype "input"))
      (node (ref "KEY1") (pin "2") (pinfunction "2_2") (pintype "unspecified"))
      (node (ref "KEY2") (pin "2") (pinfunction "2_2") (pintype "unspecified"))
      (node (ref "KEY3") (pin "2") (pinfunction "2_2") (pintype "unspecified"))
      (node (ref "KEY4") (pin "2") (pinfunction "2_2") (pintype "unspecified"))
      (node (ref "L1") (pin "2") (pinfunction "2_2") (pintype "unspecified"))
      (node (ref "LED1") (pin "1") (pinfunction "K_1") (pintype "unspecified"))
      (node (ref "LED2") (pin "1") (pinfunction "K_1") (pintype "unspecified"))
      (node (ref "OLED1") (pin "1") (pinfunction "1_1") (pintype "unspecified"))
      (node (ref "R7") (pin "1") (pinfunction "1_1") (pintype "input"))
      (node (ref "RESET1") (pin "1") (pinfunction "1_1") (pintype "unspecified"))
      (node (ref "U1") (pin "15") (pinfunction "VSS_15") (pintype "unspecified"))
      (node (ref "U1") (pin "31") (pinfunction "VSS_31") (pintype "unspecified"))
      (node (ref "U1") (pin "47") (pinfunction "VSS_47") (pintype "unspecified"))
      (node (ref "U1") (pin "63") (pinfunction "VSS_63") (pintype "unspecified"))
      (node (ref "U104") (pin "4") (pinfunction "4_4") (pintype "unspecified"))
      (node (ref "U105") (pin "1") (pinfunction "VSS_1") (pintype "unspecified"))
      (node (ref "U108") (pin "3") (pinfunction "3_3") (pintype "unspecified"))
      (node (ref "U108") (pin "4") (pinfunction "4_4") (pintype "unspecified"))
      (node (ref "U108") (pin "40") (pinfunction "40_40") (pintype "unspecified"))
    )
    (net (code "59") (name "Net-(LED1-A)") (class "Default")
      (node (ref "LED1") (pin "2") (pinfunction "A_2") (pintype "unspecified"))
      (node (ref "R2") (pin "1") (pinfunction "1_1") (pintype "input"))
    )
    (net (code "60") (name "Net-(LED2-A)") (class "Default")
      (node (ref "LED2") (pin "2") (pinfunction "A_2") (pintype "unspecified"))
      (node (ref "R15") (pin "1") (pinfunction "1_1") (pintype "input"))
    )
  )
)
